# pwr_switch.net
KiCad netlist of a schematic drawn in Altium Designer
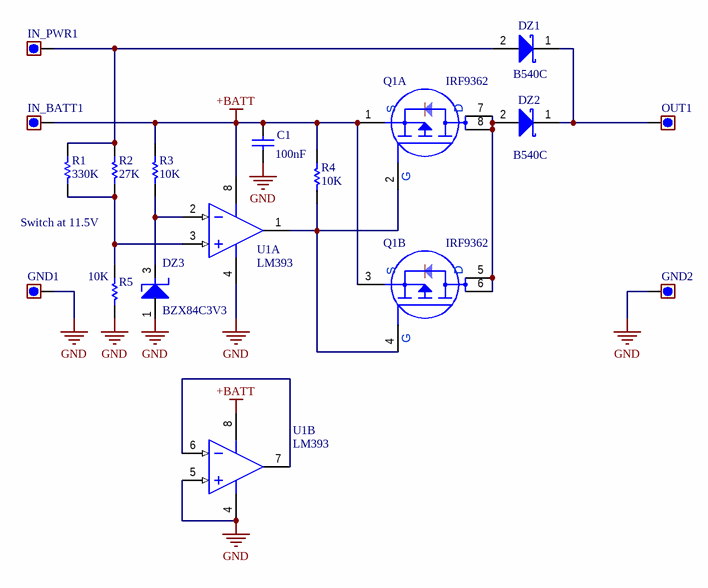
[diagram p0: pwr_switch.SchDoc]

(export (version "E")
  (design (tool "Eeschema 10.0.6"))
  (components
    (comp (ref "C1")
      (value "100nF")
      (footprint "0603_[1608]")
      (description "Capacitor")
      (fields (field (name "PUBLISHER") "Altium Limited"))
      (libsource (lib "develer_library") (part "Cap"))
    )
    (comp (ref "DZ1")
      (value "B540C")
      (footprint "DO214AB_K1-A2_SMC")
      (description "Diode Schottky (SSC54)")
      (fields (field (name "PUBLISHER") "Altium Limited"))
      (libsource (lib "Miscellaneous Devices") (part "D Schottky"))
    )
    (comp (ref "DZ2")
      (value "B540C")
      (footprint "DO214AB_K1-A2_SMC")
      (description "Diode Schottky (SSC54)")
      (fields (field (name "PUBLISHER") "Altium Limited"))
      (libsource (lib "Miscellaneous Devices") (part "D Schottky"))
    )
    (comp (ref "DZ3")
      (value "BZX84C3V3")
      (footprint "SOT-23_L")
      (description "Zener 0.35W")
      (libsource (lib "DEVELER_Library") (part "ZENER_BZX"))
    )
    (comp (ref "GND1") (value "~") (footprint "PIN1") (libsource (lib "") (part "Test_point_1")))
    (comp (ref "GND2") (value "~") (footprint "PIN1") (libsource (lib "DEVELER_Library") (part "Test_point")))
    (comp (ref "IN_BATT1") (value "~") (footprint "PIN1") (libsource (lib "") (part "Test_point_1")))
    (comp (ref "IN_PWR1") (value "~") (footprint "PIN1") (libsource (lib "") (part "Test_point_1")))
    (comp (ref "OUT1") (value "~") (footprint "PIN1") (libsource (lib "DEVELER_Library") (part "Test_point")))
    (comp (ref "Q1")
      (value "IRF9362")
      (footprint "SOIC8")
      (description "Dual channel P-MOS in same package")
      (libsource (lib "DEVELER_Library") (part "MOSFET-P dual"))
    )
    (comp (ref "R1")
      (value "330K")
      (footprint "0603_[1608]_RES_SMALL")
      (description "Resistor")
      (libsource (lib "DEVELER_Library") (part "Res1"))
    )
    (comp (ref "R2")
      (value "27K")
      (footprint "0603_[1608]_RES_SMALL")
      (description "Resistor")
      (libsource (lib "DEVELER_Library") (part "Res1"))
    )
    (comp (ref "R3")
      (value "10K")
      (footprint "0603_[1608]_RES_SMALL")
      (description "Resistor")
      (libsource (lib "DEVELER_Library") (part "Res1"))
    )
    (comp (ref "R4")
      (value "10K")
      (footprint "0603_[1608]_RES_SMALL")
      (description "Resistor")
      (libsource (lib "DEVELER_Library") (part "Res1"))
    )
    (comp (ref "R5")
      (value "10K")
      (footprint "0603_[1608]_RES_SMALL")
      (description "Resistor")
      (libsource (lib "DEVELER_Library") (part "Res1"))
    )
    (comp (ref "U1")
      (value "LM393")
      (footprint "SOIC8")
      (description "Low Offset Voltage Dual Comparators, 2 to 36 V, -40 to 105 degC, 8-Pin SOIC, Pb-Free, Tube")
      (fields (field (name "PARTNUMBER") "LM2903DG") (field (name "MANUFACTURER") "On Semiconductor"))
      (libsource (lib "develer_library") (part "LM2903DG"))
    )
  )
  (nets
    (net (code "1") (name "+BATT") (class "Default")
      (node (ref "C1") (pin "2") (pinfunction "2_2") (pintype "passive"))
      (node (ref "IN_BATT1") (pin "1") (pinfunction "1_1") (pintype "passive"))
      (node (ref "Q1") (pin "1") (pinfunction "S_1") (pintype "passive"))
      (node (ref "Q1") (pin "3") (pinfunction "S_3") (pintype "passive"))
      (node (ref "R3") (pin "2") (pinfunction "2_2") (pintype "passive"))
      (node (ref "R4") (pin "2") (pinfunction "2_2") (pintype "passive"))
      (node (ref "U1") (pin "8") (pinfunction "VCC_8") (pintype "power_in"))
    )
    (net (code "2") (name "GND") (class "Default")
      (node (ref "C1") (pin "1") (pinfunction "1_1") (pintype "passive"))
      (node (ref "DZ3") (pin "1") (pinfunction "A_1") (pintype "passive"))
      (node (ref "GND1") (pin "1") (pinfunction "1_1") (pintype "passive"))
      (node (ref "GND2") (pin "1") (pinfunction "1_1") (pintype "passive"))
      (node (ref "R5") (pin "1") (pinfunction "1_1") (pintype "passive"))
      (node (ref "U1") (pin "4") (pinfunction "GND_4") (pintype "power_in"))
      (node (ref "U1") (pin "5") (pinfunction "INB+_5") (pintype "input"))
    )
    (net (code "3") (name "Net-(DZ1-A)") (class "Default")
      (node (ref "DZ1") (pin "2") (pinfunction "A_2") (pintype "passive"))
      (node (ref "IN_PWR1") (pin "1") (pinfunction "1_1") (pintype "passive"))
      (node (ref "R1") (pin "2") (pinfunction "2_2") (pintype "passive"))
      (node (ref "R2") (pin "2") (pinfunction "2_2") (pintype "passive"))
    )
    (net (code "4") (name "Net-(DZ1-K)") (class "Default")
      (node (ref "DZ1") (pin "1") (pinfunction "K_1") (pintype "passive"))
      (node (ref "DZ2") (pin "1") (pinfunction "K_1") (pintype "passive"))
      (node (ref "OUT1") (pin "1") (pinfunction "1_1") (pintype "passive"))
    )
    (net (code "5") (name "Net-(DZ2-A)") (class "Default")
      (node (ref "DZ2") (pin "2") (pinfunction "A_2") (pintype "passive"))
      (node (ref "Q1") (pin "5") (pinfunction "D_5") (pintype "passive"))
      (node (ref "Q1") (pin "6") (pinfunction "D_6") (pintype "passive"))
      (node (ref "Q1") (pin "7") (pinfunction "D_7") (pintype "passive"))
      (node (ref "Q1") (pin "8") (pinfunction "D_8") (pintype "passive"))
    )
    (net (code "6") (name "Net-(DZ3-K)") (class "Default")
      (node (ref "DZ3") (pin "3") (pinfunction "K_3") (pintype "passive"))
      (node (ref "R3") (pin "1") (pinfunction "1_1") (pintype "passive"))
      (node (ref "U1") (pin "2") (pinfunction "INA-_2") (pintype "input"))
    )
    (net (code "7") (name "Net-(Q1A-G)") (class "Default")
      (node (ref "Q1") (pin "2") (pinfunction "G_2") (pintype "passive"))
      (node (ref "Q1") (pin "4") (pinfunction "G_4") (pintype "passive"))
      (node (ref "R4") (pin "1") (pinfunction "1_1") (pintype "passive"))
      (node (ref "U1") (pin "1") (pinfunction "OUTA_1") (pintype "open_collector"))
    )
    (net (code "8") (name "Net-(U1A-INA+)") (class "Default")
      (node (ref "R1") (pin "1") (pinfunction "1_1") (pintype "passive"))
      (node (ref "R2") (pin "1") (pinfunction "1_1") (pintype "passive"))
      (node (ref "R5") (pin "2") (pinfunction "2_2") (pintype "passive"))
      (node (ref "U1") (pin "3") (pinfunction "INA+_3") (pintype "input"))
    )
    (net (code "9") (name "Net-(U1B-INB-)") (class "Default")
      (node (ref "U1") (pin "6") (pinfunction "INB-_6") (pintype "input"))
      (node (ref "U1") (pin "7") (pinfunction "OUTB_7") (pintype "open_collector"))
    )
  )
)
